# Variable_Output_1.net
KiCad netlist of a schematic drawn in Altium Designer
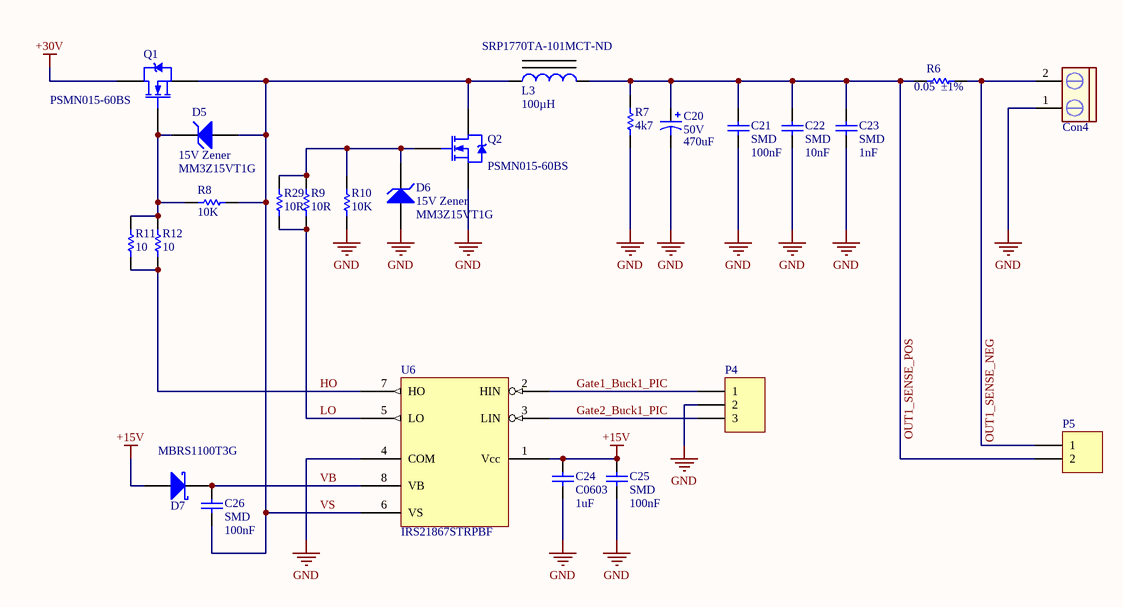
[diagram p0: Variable Output 1.SchDoc]

(export (version "E")
  (design (tool "Eeschema 10.0.6"))
  (components
    (comp (ref "C20")
      (value "50V")
      (footprint "CAPPR5-10X20")
      (description "Aluminum Electrolytic Capacitor, Radial Style with Long Leads: 470uF, 50V")
      (fields (field (name "ALTIUM_VALUE") "470uF") (field (name "PUBLISHER") "Altium Limited"))
      (libsource (lib "Vishay Roederstein Electrolytic Radial-Lead Capacitor") (part "EKB00DE347H00"))
    )
    (comp (ref "C21")
      (value "SMD")
      (footprint "1206")
      (description "Ceramic Chip Capacitor - Standard")
      (fields (field (name "ALTIUM_VALUE") "100nF") (field (name "PUBLISHER") "Altium Limited"))
      (libsource (lib "KEMET Chip Capacitor") (part "C1206"))
    )
    (comp (ref "C22")
      (value "SMD")
      (footprint "1206")
      (description "Ceramic Chip Capacitor - Standard")
      (fields (field (name "ALTIUM_VALUE") "10nF") (field (name "PUBLISHER") "Altium Limited"))
      (libsource (lib "KEMET Chip Capacitor") (part "C1206"))
    )
    (comp (ref "C23")
      (value "SMD")
      (footprint "1206")
      (description "Ceramic Chip Capacitor - Standard")
      (fields (field (name "ALTIUM_VALUE") "1nF") (field (name "PUBLISHER") "Altium Limited"))
      (libsource (lib "KEMET Chip Capacitor") (part "C1206"))
    )
    (comp (ref "C24")
      (value "C0603")
      (footprint "0603")
      (description "C1608X7R1C105K X7R")
      (fields (field (name "ALTIUM_VALUE") "1uF") (field (name "PUBLISHER") "Altium Limited"))
      (libsource (lib "KEMET Chip Capacitor") (part "C0603"))
    )
    (comp (ref "C25")
      (value "SMD")
      (footprint "1206")
      (description "Ceramic Chip Capacitor - Standard")
      (fields (field (name "ALTIUM_VALUE") "100nF") (field (name "PUBLISHER") "Altium Limited"))
      (libsource (lib "KEMET Chip Capacitor") (part "C1206"))
    )
    (comp (ref "C26")
      (value "SMD")
      (footprint "1206")
      (description "Ceramic Chip Capacitor - Standard")
      (fields (field (name "ALTIUM_VALUE") "100nF") (field (name "PUBLISHER") "Altium Limited"))
      (libsource (lib "KEMET Chip Capacitor") (part "C1206"))
    )
    (comp (ref "Con4")
      (value "Salida Buck")
      (footprint "My_CN2")
      (description "Connector blue screw")
      (libsource (lib "Mylib") (part "CON2 pin blue"))
    )
    (comp (ref "D5")
      (value "15V Zener")
      (footprint "SOD323")
      (description "Zener Diode")
      (fields
        (field (name "MANUFACTURER PART NUMBER") "MM3Z15VT1G")
        (field (name "TOLERANCE") "±5%")
        (field (name "MANUFACTURER") "ON Semiconductor")
      )
      (libsource (lib "Miscellaneous Devices") (part "D Zener"))
    )
    (comp (ref "D6")
      (value "15V Zener")
      (footprint "SOD323")
      (description "Zener Diode")
      (fields
        (field (name "MANUFACTURER PART NUMBER") "MM3Z15VT1G")
        (field (name "TOLERANCE") "±5%")
        (field (name "MANUFACTURER") "ON Semiconductor")
      )
      (libsource (lib "Miscellaneous Devices") (part "D Zener"))
    )
    (comp (ref "D7")
      (value "MBRS1100T3G")
      (footprint "SMB")
      (description "Generic Schottky Diode")
      (libsource (lib "NXT - Diodes") (part "Generic Schottky Diode"))
    )
    (comp (ref "L3")
      (value "Ferrite Inductor")
      (footprint "SRP1770TA Series")
      (fields
        (field (name "MANUFACTURER PART NUMBER") "SRP1770TA-101M")
        (field (name "TOLERANCE") "±20%")
        (field (name "SUPPLIER PART NUMBER") "SRP1770TA-101MCT-ND")
        (field (name "MANUFACTURER") "Bourns Inc.")
        (field (name "INDUCTANCE") "100µH")
      )
      (libsource (lib "NXT - Inductors") (part "Ferrite Inductor"))
    )
    (comp (ref "P4")
      (value "Header 3")
      (footprint "My_1X03")
      (description "Header, 3-Pin")
      (fields (field (name "PUBLISHER") "Altium Limited"))
      (libsource (lib "Mylib") (part "Header 3"))
    )
    (comp (ref "P5")
      (value "Header 2")
      (footprint "My_1X02")
      (description "Header, 2-Pin")
      (fields (field (name "PUBLISHER") "Altium Limited"))
      (libsource (lib "Mylib") (part "Header 2"))
    )
    (comp (ref "Q1")
      (value "SUM110P06")
      (footprint "D2PAK_N")
      (description "HEXFET Power MOSFET")
      (fields
        (field (name "MANUFACTURER PART NUMBER") "PSMN015-60BS")
        (field (name "MANUFACTURER") "Vishay Siliconix")
      )
      (libsource (lib "IR Discrete MOSFET - Power") (part "IRF540NS"))
    )
    (comp (ref "Q2")
      (value "SUM110P06")
      (footprint "D2PAK_N")
      (description "HEXFET Power MOSFET")
      (fields
        (field (name "MANUFACTURER PART NUMBER") "PSMN015-60BS")
        (field (name "MANUFACTURER") "Vishay Siliconix")
      )
      (libsource (lib "IR Discrete MOSFET - Power") (part "IRF540NS"))
    )
    (comp (ref "R6")
      (value "ERJL1W")
      (footprint "L1W-2512")
      (fields
        (field (name "MANUFACTURER PART NUMBER") "PE2512FKE070R05L")
        (field (name "MANUFACTURER") "Yageo")
        (field (name "RESISTANCE (OHMS)") "0.05")
        (field (name "TOLERANCE") "±1%")
        (field (name "PUBLISHER") "Altium Limited")
      )
      (libsource (lib "Panasonic Resistor") (part "ERJL1W"))
    )
    (comp (ref "R7")
      (value "4k7")
      (footprint "8RB-1206")
      (fields (field (name "Comment") "SMD") (field (name "PUBLISHER") "Altium Limited"))
      (libsource (lib "Panasonic Resistor") (part "ERJ8BQ"))
    )
    (comp (ref "R8")
      (value "10K")
      (footprint "ERA-0603")
      (fields (field (name "PUBLISHER") "Altium Limited"))
      (libsource (lib "Panasonic Resistor") (part "ERA3Y"))
    )
    (comp (ref "R9")
      (value "10R")
      (footprint "ERA-0603")
      (fields (field (name "PUBLISHER") "Altium Limited"))
      (libsource (lib "Panasonic Resistor") (part "ERA3Y"))
    )
    (comp (ref "R10")
      (value "10K")
      (footprint "ERA-0603")
      (fields (field (name "PUBLISHER") "Altium Limited"))
      (libsource (lib "Panasonic Resistor") (part "ERA3Y"))
    )
    (comp (ref "R11")
      (value "10")
      (footprint "ERA-0603")
      (fields (field (name "PUBLISHER") "Altium Limited"))
      (libsource (lib "Panasonic Resistor") (part "ERA3Y"))
    )
    (comp (ref "R12")
      (value "10")
      (footprint "ERA-0603")
      (fields (field (name "PUBLISHER") "Altium Limited"))
      (libsource (lib "Panasonic Resistor") (part "ERA3Y"))
    )
    (comp (ref "R29")
      (value "10R")
      (footprint "ERA-0603")
      (fields (field (name "PUBLISHER") "Altium Limited"))
      (libsource (lib "Panasonic Resistor") (part "ERA3Y"))
    )
    (comp (ref "U6")
      (value "IRS21867S")
      (footprint "SOIC8")
      (description "Half-Bridge Gate Driver IC Inverting 8-SOIC")
      (fields
        (field (name "MANUFACTURER") "Infineon Technologies")
        (field (name "MANUFACTURER PART NUMBER") "IRS21867STRPBF")
      )
      (libsource (lib "NXT - IC") (part "IRS21867S"))
    )
  )
  (nets
    (net (code "1") (name "+15V") (class "Default")
      (node (ref "C24") (pin "2") (pinfunction "2_2") (pintype "passive"))
      (node (ref "C25") (pin "2") (pinfunction "2_2") (pintype "passive"))
      (node (ref "D7") (pin "1") (pinfunction "A_1") (pintype "passive"))
      (node (ref "U6") (pin "1") (pinfunction "Vcc_1") (pintype "power_in"))
    )
    (net (code "2") (name "+30V") (class "Default")
      (node (ref "Q1") (pin "2") (pinfunction "D_2") (pintype "passive"))
    )
    (net (code "3") (name "/Gate1_Buck1_PIC") (class "Default")
      (node (ref "P4") (pin "1") (pinfunction "1_1") (pintype "passive"))
      (node (ref "U6") (pin "2") (pinfunction "HIN_2") (pintype "input"))
    )
    (net (code "4") (name "/Gate2_Buck1_PIC") (class "Default")
      (node (ref "P4") (pin "3") (pinfunction "3_3") (pintype "passive"))
      (node (ref "U6") (pin "3") (pinfunction "LIN_3") (pintype "input"))
    )
    (net (code "5") (name "/HO") (class "Default")
      (node (ref "R11") (pin "1") (pinfunction "1_1") (pintype "passive"))
      (node (ref "R12") (pin "1") (pinfunction "1_1") (pintype "passive"))
      (node (ref "U6") (pin "7") (pinfunction "HO_7") (pintype "output"))
    )
    (net (code "6") (name "/LO") (class "Default")
      (node (ref "R29") (pin "1") (pinfunction "1_1") (pintype "passive"))
      (node (ref "R9") (pin "1") (pinfunction "1_1") (pintype "passive"))
      (node (ref "U6") (pin "5") (pinfunction "LO_5") (pintype "output"))
    )
    (net (code "7") (name "/OUT1_SENSE_NEG") (class "Default")
      (node (ref "Con4") (pin "2") (pinfunction "2_2") (pintype "passive"))
      (node (ref "P5") (pin "1") (pinfunction "1_1") (pintype "passive"))
      (node (ref "R6") (pin "2") (pinfunction "2_2") (pintype "passive"))
    )
    (net (code "8") (name "/OUT1_SENSE_POS") (class "Default")
      (node (ref "C20") (pin "1") (pinfunction "1_1") (pintype "passive"))
      (node (ref "C21") (pin "2") (pinfunction "2_2") (pintype "passive"))
      (node (ref "C22") (pin "2") (pinfunction "2_2") (pintype "passive"))
      (node (ref "C23") (pin "2") (pinfunction "2_2") (pintype "passive"))
      (node (ref "L3") (pin "2") (pinfunction "2_2") (pintype "passive"))
      (node (ref "P5") (pin "2") (pinfunction "2_2") (pintype "passive"))
      (node (ref "R6") (pin "1") (pinfunction "1_1") (pintype "passive"))
      (node (ref "R7") (pin "2") (pinfunction "2_2") (pintype "passive"))
    )
    (net (code "9") (name "/VB") (class "Default")
      (node (ref "C26") (pin "2") (pinfunction "2_2") (pintype "passive"))
      (node (ref "D7") (pin "2") (pinfunction "K_2") (pintype "passive"))
      (node (ref "U6") (pin "8") (pinfunction "VB_8") (pintype "passive"))
    )
    (net (code "10") (name "/VS") (class "Default")
      (node (ref "C26") (pin "1") (pinfunction "1_1") (pintype "passive"))
      (node (ref "D5") (pin "1") (pinfunction "A_1") (pintype "passive"))
      (node (ref "L3") (pin "1") (pinfunction "1_1") (pintype "passive"))
      (node (ref "Q1") (pin "3") (pinfunction "S_3") (pintype "passive"))
      (node (ref "Q2") (pin "2") (pinfunction "D_2") (pintype "passive"))
      (node (ref "R8") (pin "2") (pinfunction "2_2") (pintype "passive"))
      (node (ref "U6") (pin "6") (pinfunction "VS_6") (pintype "passive"))
    )
    (net (code "11") (name "GND") (class "Default")
      (node (ref "C20") (pin "2") (pinfunction "2_2") (pintype "passive"))
      (node (ref "C21") (pin "1") (pinfunction "1_1") (pintype "passive"))
      (node (ref "C22") (pin "1") (pinfunction "1_1") (pintype "passive"))
      (node (ref "C23") (pin "1") (pinfunction "1_1") (pintype "passive"))
      (node (ref "C24") (pin "1") (pinfunction "1_1") (pintype "passive"))
      (node (ref "C25") (pin "1") (pinfunction "1_1") (pintype "passive"))
      (node (ref "Con4") (pin "1") (pinfunction "1_1") (pintype "passive"))
      (node (ref "D6") (pin "1") (pinfunction "A_1") (pintype "passive"))
      (node (ref "P4") (pin "2") (pinfunction "2_2") (pintype "passive"))
      (node (ref "Q2") (pin "3") (pinfunction "S_3") (pintype "passive"))
      (node (ref "R10") (pin "1") (pinfunction "1_1") (pintype "passive"))
      (node (ref "R7") (pin "1") (pinfunction "1_1") (pintype "passive"))
      (node (ref "U6") (pin "4") (pinfunction "COM_4") (pintype "passive"))
    )
    (net (code "12") (name "Net-(D5-K)") (class "Default")
      (node (ref "D5") (pin "2") (pinfunction "K_2") (pintype "passive"))
      (node (ref "Q1") (pin "1") (pinfunction "G_1") (pintype "passive"))
      (node (ref "R11") (pin "2") (pinfunction "2_2") (pintype "passive"))
      (node (ref "R12") (pin "2") (pinfunction "2_2") (pintype "passive"))
      (node (ref "R8") (pin "1") (pinfunction "1_1") (pintype "passive"))
    )
    (net (code "13") (name "Net-(D6-K)") (class "Default")
      (node (ref "D6") (pin "2") (pinfunction "K_2") (pintype "passive"))
      (node (ref "Q2") (pin "1") (pinfunction "G_1") (pintype "passive"))
      (node (ref "R10") (pin "2") (pinfunction "2_2") (pintype "passive"))
      (node (ref "R29") (pin "2") (pinfunction "2_2") (pintype "passive"))
      (node (ref "R9") (pin "2") (pinfunction "2_2") (pintype "passive"))
    )
  )
)
